# Part03_MT7688_Peripheral.net
KiCad netlist of a schematic drawn in Altium Designer
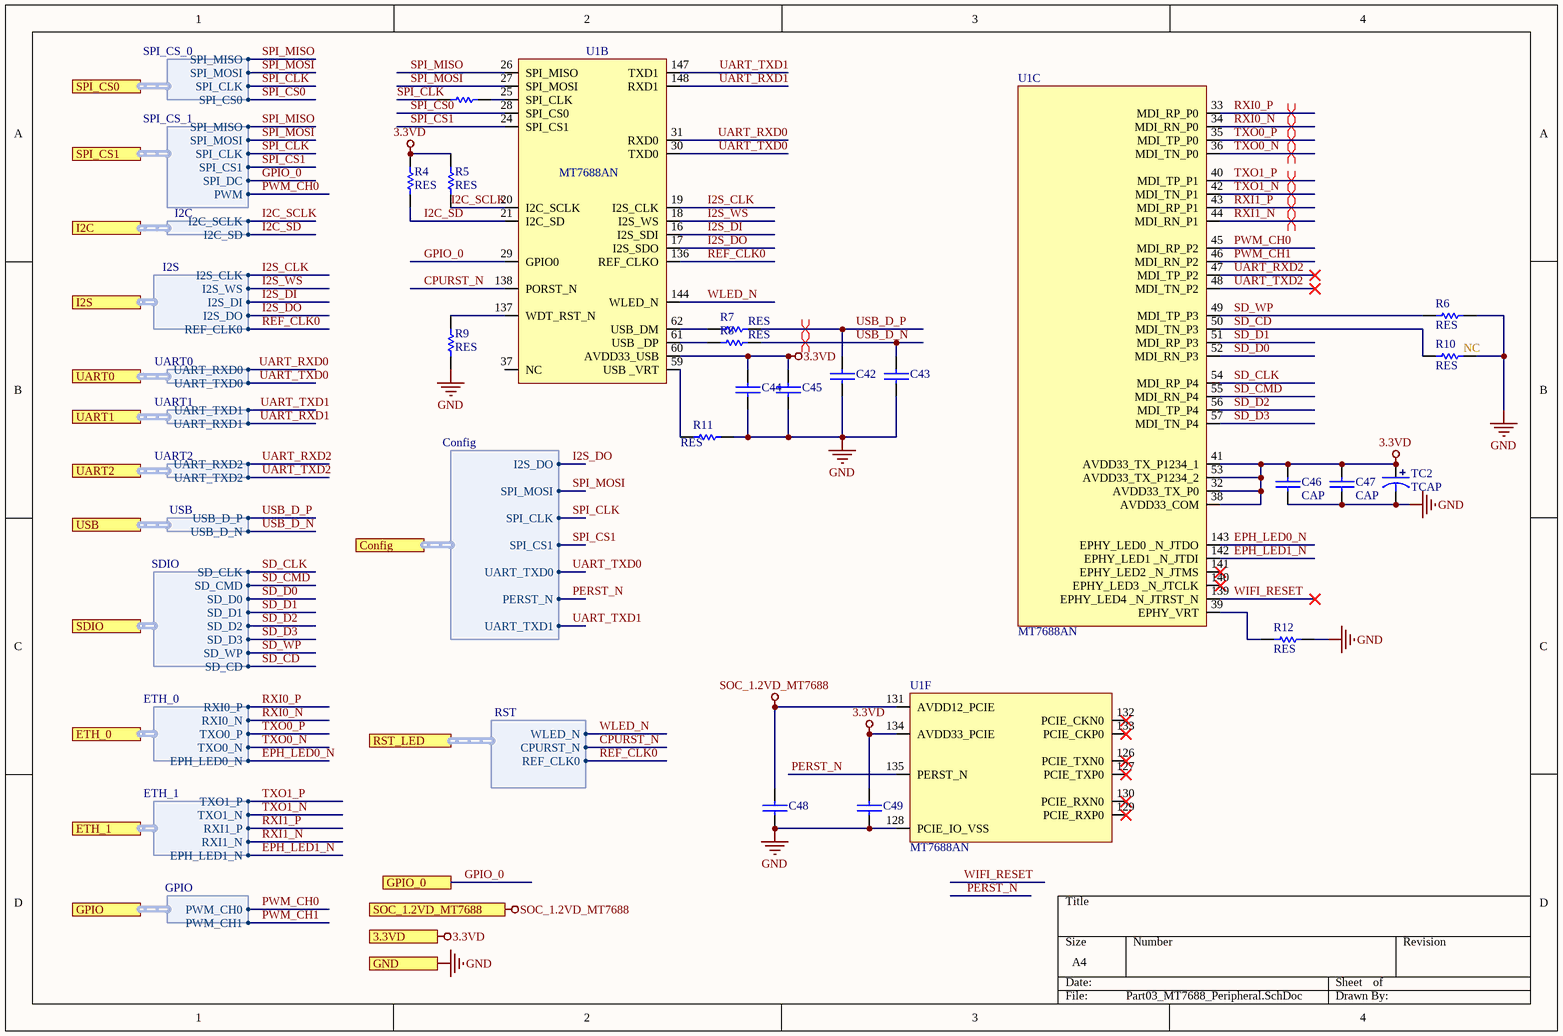
[diagram p0: Part03_MT7688_Peripheral.SchDoc]

(export (version "E")
  (design (tool "Eeschema 10.0.6"))
  (components
    (comp (ref "C42")
      (value "CAP")
      (footprint "0402C")
      (description "无极性电容")
      (libsource (lib "电容") (part "CAP"))
    )
    (comp (ref "C43")
      (value "CAP")
      (footprint "0402C")
      (description "无极性电容")
      (libsource (lib "电容") (part "CAP"))
    )
    (comp (ref "C44")
      (value "CAP")
      (footprint "0402C")
      (description "无极性电容")
      (libsource (lib "电容") (part "CAP"))
    )
    (comp (ref "C45")
      (value "CAP")
      (footprint "0402C")
      (description "无极性电容")
      (libsource (lib "电容") (part "CAP"))
    )
    (comp (ref "C46")
      (value "CAP")
      (footprint "0402C")
      (description "无极性电容")
      (libsource (lib "电容") (part "CAP"))
    )
    (comp (ref "C47")
      (value "CAP")
      (footprint "0402C")
      (description "无极性电容")
      (libsource (lib "电容") (part "CAP"))
    )
    (comp (ref "C48")
      (value "CAP")
      (footprint "0402C")
      (description "无极性电容")
      (libsource (lib "电容") (part "CAP"))
    )
    (comp (ref "C49")
      (value "CAP")
      (footprint "0402C")
      (description "无极性电容")
      (libsource (lib "电容") (part "CAP"))
    )
    (comp (ref "R3") (value "RES") (footprint "0402R") (libsource (lib "电阻") (part "RES")))
    (comp (ref "R4") (value "RES") (footprint "0402R") (libsource (lib "电阻") (part "RES")))
    (comp (ref "R5") (value "RES") (footprint "0402R") (libsource (lib "电阻") (part "RES")))
    (comp (ref "R6") (value "RES") (footprint "0402R") (libsource (lib "电阻") (part "RES")))
    (comp (ref "R7") (value "RES") (footprint "0402R") (libsource (lib "电阻") (part "RES")))
    (comp (ref "R8") (value "RES") (footprint "0402R") (libsource (lib "电阻") (part "RES")))
    (comp (ref "R9") (value "RES") (footprint "0402R") (libsource (lib "电阻") (part "RES")))
    (comp (ref "R10") (value "RES") (footprint "0402R") (libsource (lib "电阻") (part "RES")))
    (comp (ref "R11") (value "RES") (footprint "0402R") (libsource (lib "电阻") (part "RES")))
    (comp (ref "R12") (value "RES") (footprint "0402R") (libsource (lib "电阻") (part "RES")))
    (comp (ref "TC2")
      (value "TCAP")
      (footprint "TAJ-A/3216")
      (description "钽电容")
      (libsource (lib "电容") (part "TCAP"))
    )
    (comp (ref "U1")
      (value "MT7688AN")
      (footprint "MT7628AN$2F$DRQFN156$2F$SMD$2F$P0.5$2F$12X12")
      (libsource (lib "MT7688_Lib") (part "MT7688AN"))
    )
  )
  (nets
    (net (code "15") (name "/CPURST_N") (class "Default")
      (node (ref "U1") (pin "138") (pinfunction "PORST_N_138") (pintype "passive"))
    )
    (net (code "16") (name "/EPH_LED0_N") (class "Default")
      (node (ref "U1") (pin "143") (pinfunction "EPHY_LED0__N_JTDO_143") (pintype "passive"))
    )
    (net (code "17") (name "/EPH_LED1_N") (class "Default")
      (node (ref "U1") (pin "142") (pinfunction "EPHY_LED1__N_JTDI_142") (pintype "passive"))
    )
    (net (code "18") (name "/GPIO_0") (class "Default")
      (node (ref "U1") (pin "29") (pinfunction "GPIO0_29") (pintype "passive"))
    )
    (net (code "19") (name "/I2C_SCLK") (class "Default")
      (node (ref "R5") (pin "1") (pinfunction "1_1") (pintype "passive"))
      (node (ref "U1") (pin "20") (pinfunction "I2C_SCLK_20") (pintype "passive"))
    )
    (net (code "20") (name "/I2C_SD") (class "Default")
      (node (ref "R4") (pin "1") (pinfunction "1_1") (pintype "passive"))
      (node (ref "U1") (pin "21") (pinfunction "I2C_SD_21") (pintype "passive"))
    )
    (net (code "21") (name "/I2S_CLK") (class "Default")
      (node (ref "U1") (pin "19") (pinfunction "I2S_CLK_19") (pintype "passive"))
    )
    (net (code "22") (name "/I2S_DI") (class "Default")
      (node (ref "U1") (pin "16") (pinfunction "I2S_SDI_16") (pintype "passive"))
    )
    (net (code "23") (name "/I2S_DO") (class "Default")
      (node (ref "U1") (pin "17") (pinfunction "I2S_SDO_17") (pintype "passive"))
    )
    (net (code "24") (name "/I2S_WS") (class "Default")
      (node (ref "U1") (pin "18") (pinfunction "I2S_WS_18") (pintype "passive"))
    )
    (net (code "25") (name "/PERST_N") (class "Default")
      (node (ref "U1") (pin "135") (pinfunction "PERST_N_135") (pintype "passive"))
    )
    (net (code "26") (name "/PWM_CH0") (class "Default")
      (node (ref "U1") (pin "45") (pinfunction "MDI_RP_P2_45") (pintype "passive"))
    )
    (net (code "27") (name "/PWM_CH1") (class "Default")
      (node (ref "U1") (pin "46") (pinfunction "MDI_RN_P2_46") (pintype "passive"))
    )
    (net (code "28") (name "/REF_CLK0") (class "Default")
      (node (ref "U1") (pin "136") (pinfunction "REF_CLKO_136") (pintype "passive"))
    )
    (net (code "29") (name "/RXI0_N") (class "Default")
      (node (ref "U1") (pin "34") (pinfunction "MDI_RN_P0_34") (pintype "passive"))
    )
    (net (code "30") (name "/RXI0_P") (class "Default")
      (node (ref "U1") (pin "33") (pinfunction "MDI_RP_P0_33") (pintype "passive"))
    )
    (net (code "31") (name "/RXI1_N") (class "Default")
      (node (ref "U1") (pin "44") (pinfunction "MDI_RN_P1_44") (pintype "passive"))
    )
    (net (code "32") (name "/RXI1_P") (class "Default")
      (node (ref "U1") (pin "43") (pinfunction "MDI_RP_P1_43") (pintype "passive"))
    )
    (net (code "33") (name "/SD_CD") (class "Default")
      (node (ref "R10") (pin "2") (pinfunction "2_2") (pintype "passive"))
      (node (ref "U1") (pin "50") (pinfunction "MDI_TN_P3_50") (pintype "passive"))
    )
    (net (code "34") (name "/SD_CLK") (class "Default")
      (node (ref "U1") (pin "54") (pinfunction "MDI_RP_P4_54") (pintype "passive"))
    )
    (net (code "35") (name "/SD_CMD") (class "Default")
      (node (ref "U1") (pin "55") (pinfunction "MDI_RN_P4_55") (pintype "passive"))
    )
    (net (code "36") (name "/SD_D0") (class "Default")
      (node (ref "U1") (pin "52") (pinfunction "MDI_RN_P3_52") (pintype "passive"))
    )
    (net (code "37") (name "/SD_D1") (class "Default")
      (node (ref "U1") (pin "51") (pinfunction "MDI_RP_P3_51") (pintype "passive"))
    )
    (net (code "38") (name "/SD_D2") (class "Default")
      (node (ref "U1") (pin "56") (pinfunction "MDI_TP_P4_56") (pintype "passive"))
    )
    (net (code "39") (name "/SD_D3") (class "Default")
      (node (ref "U1") (pin "57") (pinfunction "MDI_TN_P4_57") (pintype "passive"))
    )
    (net (code "40") (name "/SD_WP") (class "Default")
      (node (ref "R6") (pin "2") (pinfunction "2_2") (pintype "passive"))
      (node (ref "U1") (pin "49") (pinfunction "MDI_TP_P3_49") (pintype "passive"))
    )
    (net (code "41") (name "/SPI_CLK") (class "Default")
      (node (ref "R3") (pin "2") (pinfunction "2_2") (pintype "passive"))
    )
    (net (code "42") (name "/SPI_CS0") (class "Default")
      (node (ref "U1") (pin "28") (pinfunction "SPI_CS0_28") (pintype "passive"))
    )
    (net (code "43") (name "/SPI_CS1") (class "Default")
      (node (ref "U1") (pin "24") (pinfunction "SPI_CS1_24") (pintype "passive"))
    )
    (net (code "45") (name "/SPI_MISO") (class "Default")
      (node (ref "U1") (pin "26") (pinfunction "SPI_MISO_26") (pintype "passive"))
    )
    (net (code "46") (name "/SPI_MOSI") (class "Default")
      (node (ref "U1") (pin "27") (pinfunction "SPI_MOSI_27") (pintype "passive"))
    )
    (net (code "47") (name "/TXO0_N") (class "Default")
      (node (ref "U1") (pin "36") (pinfunction "MDI_TN_P0_36") (pintype "passive"))
    )
    (net (code "48") (name "/TXO0_P") (class "Default")
      (node (ref "U1") (pin "35") (pinfunction "MDI_TP_P0_35") (pintype "passive"))
    )
    (net (code "49") (name "/TXO1_N") (class "Default")
      (node (ref "U1") (pin "42") (pinfunction "MDI_TN_P1_42") (pintype "passive"))
    )
    (net (code "50") (name "/TXO1_P") (class "Default")
      (node (ref "U1") (pin "40") (pinfunction "MDI_TP_P1_40") (pintype "passive"))
    )
    (net (code "51") (name "/UART_RXD0") (class "Default")
      (node (ref "U1") (pin "31") (pinfunction "RXD0_31") (pintype "passive"))
    )
    (net (code "52") (name "/UART_RXD1") (class "Default")
      (node (ref "U1") (pin "148") (pinfunction "RXD1_148") (pintype "passive"))
    )
    (net (code "53") (name "/UART_RXD2") (class "Default")
      (node (ref "U1") (pin "47") (pinfunction "MDI_TP_P2_47") (pintype "passive"))
    )
    (net (code "54") (name "/UART_TXD0") (class "Default")
      (node (ref "U1") (pin "30") (pinfunction "TXD0_30") (pintype "passive"))
    )
    (net (code "55") (name "/UART_TXD1") (class "Default")
      (node (ref "U1") (pin "147") (pinfunction "TXD1_147") (pintype "passive"))
    )
    (net (code "56") (name "/UART_TXD2") (class "Default")
      (node (ref "U1") (pin "48") (pinfunction "MDI_TN_P2_48") (pintype "passive"))
    )
    (net (code "57") (name "/USB_D_N") (class "Default")
      (node (ref "C43") (pin "1") (pinfunction "1_1") (pintype "passive"))
      (node (ref "R8") (pin "1") (pinfunction "1_1") (pintype "passive"))
    )
    (net (code "58") (name "/USB_D_P") (class "Default")
      (node (ref "C42") (pin "1") (pinfunction "1_1") (pintype "passive"))
      (node (ref "R7") (pin "1") (pinfunction "1_1") (pintype "passive"))
    )
    (net (code "59") (name "/WIFI_RESET") (class "Default")
      (node (ref "U1") (pin "139") (pinfunction "EPHY_LED4__N_JTRST_N_139") (pintype "passive"))
    )
    (net (code "60") (name "/WLED_N") (class "Default")
      (node (ref "U1") (pin "144") (pinfunction "WLED_N_144") (pintype "passive"))
    )
    (net (code "74") (name "3.3VD") (class "Default")
      (node (ref "C44") (pin "1") (pinfunction "1_1") (pintype "passive"))
      (node (ref "C45") (pin "1") (pinfunction "1_1") (pintype "passive"))
      (node (ref "C46") (pin "1") (pinfunction "1_1") (pintype "passive"))
      (node (ref "C47") (pin "1") (pinfunction "1_1") (pintype "passive"))
      (node (ref "C49") (pin "1") (pinfunction "1_1") (pintype "passive"))
      (node (ref "R4") (pin "2") (pinfunction "2_2") (pintype "passive"))
      (node (ref "R5") (pin "2") (pinfunction "2_2") (pintype "passive"))
      (node (ref "TC2") (pin "1") (pinfunction "1_1") (pintype "passive"))
      (node (ref "U1") (pin "134") (pinfunction "AVDD33_PCIE_134") (pintype "passive"))
      (node (ref "U1") (pin "32") (pinfunction "AVDD33_TX_P0_32") (pintype "passive"))
      (node (ref "U1") (pin "38") (pinfunction "AVDD33_COM_38") (pintype "passive"))
      (node (ref "U1") (pin "41") (pinfunction "AVDD33_TX_P1234_1_41") (pintype "passive"))
      (node (ref "U1") (pin "53") (pinfunction "AVDD33_TX_P1234_2_53") (pintype "passive"))
      (node (ref "U1") (pin "60") (pinfunction "AVDD33_USB_60") (pintype "passive"))
    )
    (net (code "75") (name "GND") (class "Default")
      (node (ref "C42") (pin "2") (pinfunction "2_2") (pintype "passive"))
      (node (ref "C43") (pin "2") (pinfunction "2_2") (pintype "passive"))
      (node (ref "C44") (pin "2") (pinfunction "2_2") (pintype "passive"))
      (node (ref "C45") (pin "2") (pinfunction "2_2") (pintype "passive"))
      (node (ref "C46") (pin "2") (pinfunction "2_2") (pintype "passive"))
      (node (ref "C47") (pin "2") (pinfunction "2_2") (pintype "passive"))
      (node (ref "C48") (pin "2") (pinfunction "2_2") (pintype "passive"))
      (node (ref "C49") (pin "2") (pinfunction "2_2") (pintype "passive"))
      (node (ref "R10") (pin "1") (pinfunction "1_1") (pintype "passive"))
      (node (ref "R11") (pin "1") (pinfunction "1_1") (pintype "passive"))
      (node (ref "R12") (pin "1") (pinfunction "1_1") (pintype "passive"))
      (node (ref "R6") (pin "1") (pinfunction "1_1") (pintype "passive"))
      (node (ref "R9") (pin "1") (pinfunction "1_1") (pintype "passive"))
      (node (ref "TC2") (pin "2") (pinfunction "2_2") (pintype "passive"))
      (node (ref "U1") (pin "128") (pinfunction "PCIE_IO_VSS_128") (pintype "passive"))
    )
    (net (code "76") (name "Net-(U1B-SPI_CLK)") (class "Default")
      (node (ref "R3") (pin "1") (pinfunction "1_1") (pintype "passive"))
      (node (ref "U1") (pin "25") (pinfunction "SPI_CLK_25") (pintype "passive"))
    )
    (net (code "77") (name "Net-(U1B-USB_DM)") (class "Default")
      (node (ref "R7") (pin "2") (pinfunction "2_2") (pintype "passive"))
      (node (ref "U1") (pin "62") (pinfunction "USB_DM_62") (pintype "passive"))
    )
    (net (code "78") (name "Net-(U1B-USB__DP)") (class "Default")
      (node (ref "R8") (pin "2") (pinfunction "2_2") (pintype "passive"))
      (node (ref "U1") (pin "61") (pinfunction "USB__DP_61") (pintype "passive"))
    )
    (net (code "79") (name "Net-(U1B-USB__VRT)") (class "Default")
      (node (ref "R11") (pin "2") (pinfunction "2_2") (pintype "passive"))
      (node (ref "U1") (pin "59") (pinfunction "USB__VRT_59") (pintype "passive"))
    )
    (net (code "80") (name "Net-(U1B-WDT_RST_N)") (class "Default")
      (node (ref "R9") (pin "2") (pinfunction "2_2") (pintype "passive"))
      (node (ref "U1") (pin "137") (pinfunction "WDT_RST_N_137") (pintype "passive"))
    )
    (net (code "81") (name "Net-(U1C-EPHY_VRT)") (class "Default")
      (node (ref "R12") (pin "2") (pinfunction "2_2") (pintype "passive"))
      (node (ref "U1") (pin "39") (pinfunction "EPHY_VRT_39") (pintype "passive"))
    )
    (net (code "82") (name "SOC_1.2VD_MT7688") (class "Default")
      (node (ref "C48") (pin "1") (pinfunction "1_1") (pintype "passive"))
      (node (ref "U1") (pin "131") (pinfunction "AVDD12_PCIE_131") (pintype "passive"))
    )
    (net (code "83") (name "unconnected-(U1B-NC-Pad37)") (class "Default")
      (node (ref "U1") (pin "37") (pinfunction "NC_37") (pintype "passive"))
    )
    (net (code "84") (name "unconnected-(U1C-EPHY_LED2__N_JTMS-Pad141)") (class "Default")
      (node (ref "U1") (pin "141") (pinfunction "EPHY_LED2__N_JTMS_141") (pintype "passive+no_connect"))
    )
    (net (code "85") (name "unconnected-(U1C-EPHY_LED3__N_JTCLK-Pad140)") (class "Default")
      (node (ref "U1") (pin "140") (pinfunction "EPHY_LED3__N_JTCLK_140") (pintype "passive+no_connect"))
    )
    (net (code "86") (name "unconnected-(U1F-PCIE_CKN0-Pad132)") (class "Default")
      (node (ref "U1") (pin "132") (pinfunction "PCIE_CKN0_132") (pintype "passive+no_connect"))
    )
    (net (code "87") (name "unconnected-(U1F-PCIE_CKP0-Pad133)") (class "Default")
      (node (ref "U1") (pin "133") (pinfunction "PCIE_CKP0_133") (pintype "passive+no_connect"))
    )
    (net (code "88") (name "unconnected-(U1F-PCIE_RXN0-Pad130)") (class "Default")
      (node (ref "U1") (pin "130") (pinfunction "PCIE_RXN0_130") (pintype "passive+no_connect"))
    )
    (net (code "89") (name "unconnected-(U1F-PCIE_RXP0-Pad129)") (class "Default")
      (node (ref "U1") (pin "129") (pinfunction "PCIE_RXP0_129") (pintype "passive+no_connect"))
    )
    (net (code "90") (name "unconnected-(U1F-PCIE_TXN0-Pad126)") (class "Default")
      (node (ref "U1") (pin "126") (pinfunction "PCIE_TXN0_126") (pintype "passive+no_connect"))
    )
    (net (code "91") (name "unconnected-(U1F-PCIE_TXP0-Pad127)") (class "Default")
      (node (ref "U1") (pin "127") (pinfunction "PCIE_TXP0_127") (pintype "passive+no_connect"))
    )
  )
)
